# BMS.net
KiCad netlist of a schematic drawn in Altium Designer
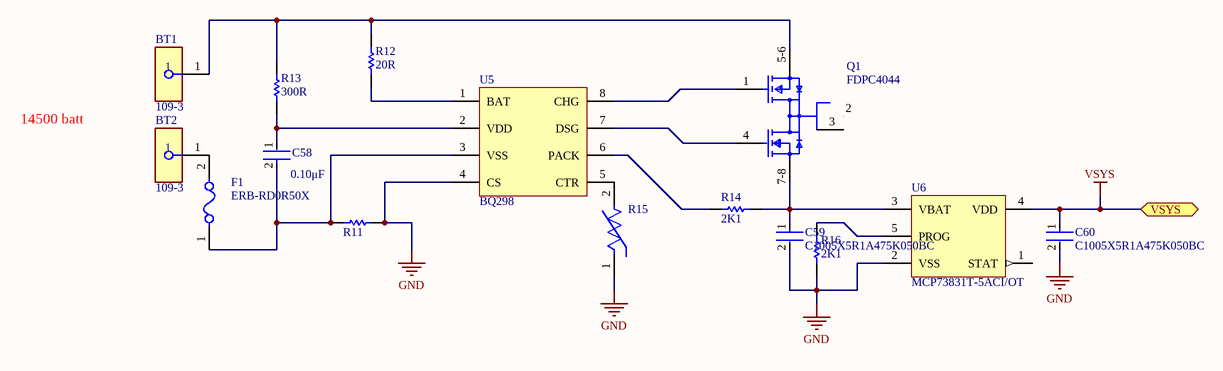
[diagram p0: BMS.SchDoc]

(export (version "E")
  (design (tool "Eeschema 10.0.6"))
  (components
    (comp (ref "BT1")
      (value "109-3")
      (footprint "FP-109-3-MFG")
      (description "BATT CONTACT SPRING MULTI PC PIN")
      (libsource (lib "Altium Content Vault") (part "c5c826e0c4b67fe3b42ef77f2d4decc"))
    )
    (comp (ref "BT2")
      (value "109-3")
      (footprint "FP-109-3-MFG")
      (description "BATT CONTACT SPRING MULTI PC PIN")
      (libsource (lib "Altium Content Vault") (part "c5c826e0c4b67fe3b42ef77f2d4decc"))
    )
    (comp (ref "C58")
      (value "GRM155R71C104KA88D")
      (footprint "FP-GRM15-MFG")
      (description "CAP CER 0.1UF 16V X7R 0402")
      (fields
        (field (name "TOLERANCE") "10%")
        (field (name "OCTOPART") "https://octopart.com/grm155r71c104ka88d-murata-196880")
        (field (name "CAPACITANCE") "0.10μF")
      )
      (libsource (lib "Altium Content Vault") (part "236180d848d6139a670b325ea6854c9"))
    )
    (comp (ref "C59")
      (value "C1005X5R1A475K050BC")
      (footprint "FP-C1005-050-0_15-MFG")
      (description "CAP CER 4.7UF 10V X5R 0402")
      (fields (field (name "TOLERANCE") "10%"))
      (libsource (lib "Altium Content Vault") (part "b4654b650e69147ec39a6b967a45e02"))
    )
    (comp (ref "C60")
      (value "C1005X5R1A475K050BC")
      (footprint "FP-C1005-050-0_15-MFG")
      (description "CAP CER 4.7UF 10V X5R 0402")
      (fields (field (name "TOLERANCE") "10%"))
      (libsource (lib "Altium Content Vault") (part "b4654b650e69147ec39a6b967a45e02"))
    )
    (comp (ref "F1")
      (value "ERB-RD0R50X")
      (footprint "FP-ERBRD-MFG")
      (description "FUSE BOARD MNT 500MA 32VDC 0402")
      (fields
        (field (name "MANUFACTURER") "Panasonic Electronic Components")
        (field (name "OCTOPART") "https://octopart.com/erb-rd0r50x-panasonic-21220527")
      )
      (libsource (lib "Altium Content Vault") (part "5bcf9b9f640e542cf0359d10258e979"))
    )
    (comp (ref "Q1")
      (value "FDPC4044")
      (footprint "FP-483BP-MFG")
      (description "MOSFET 2N-CH 8MLP")
      (fields
        (field (name "OCTOPART") "https://octopart.com/fdpc4044-on+semiconductor-84326487")
        (field (name "MANUFACTURER") "ON Semiconductor")
      )
      (libsource (lib "Altium Content Vault") (part "66ce4998423d119a94938075f396399"))
    )
    (comp (ref "R11")
      (value "ERJ-2BSFR10X")
      (footprint "RESC1005X40X27LL10T10")
      (fields (field (name "MANUFACTURER") "Panasonic"))
      (libsource (lib "Altium Content Vault") (part "RES"))
    )
    (comp (ref "R12")
      (value "20R")
      (footprint "RESC1005X40X25LL05T10")
      (fields (field (name "PART NUMBER") "RC0402FR-0720RL") (field (name "MANUFACTURER") "Yageo / Phycomp"))
      (libsource (lib "Altium Content Vault") (part "RES"))
    )
    (comp (ref "R13")
      (value "300R")
      (footprint "RESC1005X35X20ML05T10")
      (fields
        (field (name "PART NUMBER") "CPF0402B300RE1")
        (field (name "MANUFACTURER") "TE Connectivity / AMP")
      )
      (libsource (lib "Altium Content Vault") (part "RES"))
    )
    (comp (ref "R14")
      (value "2K1")
      (footprint "RESC1005X40X25NL05T05")
      (fields (field (name "PART NUMBER") "CRCW04022K10FKED") (field (name "MANUFACTURER") "Vishay Dale"))
      (libsource (lib "Altium Content Vault") (part "RES"))
    )
    (comp (ref "R15")
      (value "NCP15XH103F03RC")
      (footprint "FP-NCP15-NCU15-0_05-IPC_C")
      (description "NTC Thermistor for Temperature Sensor, 0402, 10kΩ, 1%, 0.1mA, 5V")
      (fields (field (name "TOLERANCE") "1%"))
      (libsource (lib "Altium Content Vault") (part "3b148a6ebabc5fb4d708a66c052d352"))
    )
    (comp (ref "R16")
      (value "2K1")
      (footprint "RESC1005X40X25NL05T05")
      (fields (field (name "PART NUMBER") "CRCW04022K10FKED") (field (name "MANUFACTURER") "Vishay Dale"))
      (libsource (lib "Altium Content Vault") (part "RES"))
    )
    (comp (ref "U5") (value "BQ298") (footprint "thingio") (libsource (lib "PMIC") (part "BQ298")))
    (comp (ref "U6")
      (value "MCP73831T-5ACI/OT")
      (footprint "SOT-23-OT5_N")
      (libsource (lib "Altium Content Vault") (part "PM-BM-MCP73831-SOT5"))
    )
  )
  (nets
    (net (code "1") (name "GND") (class "Default")
      (node (ref "C59") (pin "2") (pinfunction "2_2") (pintype "passive"))
      (node (ref "C60") (pin "2") (pinfunction "2_2") (pintype "passive"))
      (node (ref "R11") (pin "1") (pinfunction "1_1") (pintype "passive"))
      (node (ref "R15") (pin "1") (pinfunction "1_1") (pintype "passive"))
      (node (ref "R16") (pin "1") (pinfunction "1_1") (pintype "passive"))
      (node (ref "U5") (pin "4") (pinfunction "CS_4") (pintype "passive"))
      (node (ref "U6") (pin "2") (pinfunction "VSS_2") (pintype "power_in"))
    )
    (net (code "2") (name "Net-(BT2-Pad1)") (class "Default")
      (node (ref "BT2") (pin "1") (pinfunction "1_1") (pintype "passive"))
      (node (ref "F1") (pin "2") (pinfunction "2_2") (pintype "passive"))
    )
    (net (code "3") (name "Net-(Q1-G1)") (class "Default")
      (node (ref "Q1") (pin "1") (pinfunction "G1_1") (pintype "passive"))
      (node (ref "U5") (pin "8") (pinfunction "CHG_8") (pintype "passive"))
    )
    (net (code "4") (name "Net-(Q1-G2)") (class "Default")
      (node (ref "Q1") (pin "4") (pinfunction "G2_4") (pintype "passive"))
      (node (ref "U5") (pin "7") (pinfunction "DSG_7") (pintype "passive"))
    )
    (net (code "5") (name "Net-(Q1-S1)") (class "Default")
      (node (ref "BT1") (pin "1") (pinfunction "1_1") (pintype "passive"))
      (node (ref "Q1") (pin "5-6") (pinfunction "S1_5-6") (pintype "passive"))
      (node (ref "R12") (pin "2") (pinfunction "2_2") (pintype "passive"))
      (node (ref "R13") (pin "2") (pinfunction "2_2") (pintype "passive"))
    )
    (net (code "6") (name "Net-(Q1-S2)") (class "Default")
      (node (ref "C59") (pin "1") (pinfunction "1_1") (pintype "passive"))
      (node (ref "Q1") (pin "7-8") (pinfunction "S2_7-8") (pintype "passive"))
      (node (ref "R14") (pin "2") (pinfunction "2_2") (pintype "passive"))
      (node (ref "U6") (pin "3") (pinfunction "VBAT_3") (pintype "power_in"))
    )
    (net (code "7") (name "Net-(U5-BAT)") (class "Default")
      (node (ref "R12") (pin "1") (pinfunction "1_1") (pintype "passive"))
      (node (ref "U5") (pin "1") (pinfunction "BAT_1") (pintype "passive"))
    )
    (net (code "8") (name "Net-(U5-CTR)") (class "Default")
      (node (ref "R15") (pin "2") (pinfunction "2_2") (pintype "passive"))
      (node (ref "U5") (pin "5") (pinfunction "CTR_5") (pintype "passive"))
    )
    (net (code "9") (name "Net-(U5-PACK)") (class "Default")
      (node (ref "R14") (pin "1") (pinfunction "1_1") (pintype "passive"))
      (node (ref "U5") (pin "6") (pinfunction "PACK_6") (pintype "passive"))
    )
    (net (code "10") (name "Net-(U5-VDD)") (class "Default")
      (node (ref "C58") (pin "1") (pinfunction "1_1") (pintype "passive"))
      (node (ref "R13") (pin "1") (pinfunction "1_1") (pintype "passive"))
      (node (ref "U5") (pin "2") (pinfunction "VDD_2") (pintype "passive"))
    )
    (net (code "11") (name "Net-(U5-VSS)") (class "Default")
      (node (ref "C58") (pin "2") (pinfunction "2_2") (pintype "passive"))
      (node (ref "F1") (pin "1") (pinfunction "1_1") (pintype "passive"))
      (node (ref "R11") (pin "2") (pinfunction "2_2") (pintype "passive"))
      (node (ref "U5") (pin "3") (pinfunction "VSS_3") (pintype "passive"))
    )
    (net (code "12") (name "Net-(U6-PROG)") (class "Default")
      (node (ref "R16") (pin "2") (pinfunction "2_2") (pintype "passive"))
      (node (ref "U6") (pin "5") (pinfunction "PROG_5") (pintype "passive"))
    )
    (net (code "13") (name "VSYS") (class "Default")
      (node (ref "C60") (pin "1") (pinfunction "1_1") (pintype "passive"))
      (node (ref "U6") (pin "4") (pinfunction "VDD_4") (pintype "power_in"))
    )
    (net (code "14") (name "unconnected-(Q1-D1-Pad2)") (class "Default")
      (node (ref "Q1") (pin "2") (pinfunction "D1_2") (pintype "passive"))
    )
    (net (code "15") (name "unconnected-(Q1-D2-Pad3)") (class "Default")
      (node (ref "Q1") (pin "3") (pinfunction "D2_3") (pintype "passive"))
    )
    (net (code "16") (name "unconnected-(U6-STAT-Pad1)") (class "Default")
      (node (ref "U6") (pin "1") (pinfunction "STAT_1") (pintype "output"))
    )
  )
)
